# Carrier-Board-CM740.net
KiCad netlist of a schematic drawn in EAGLE
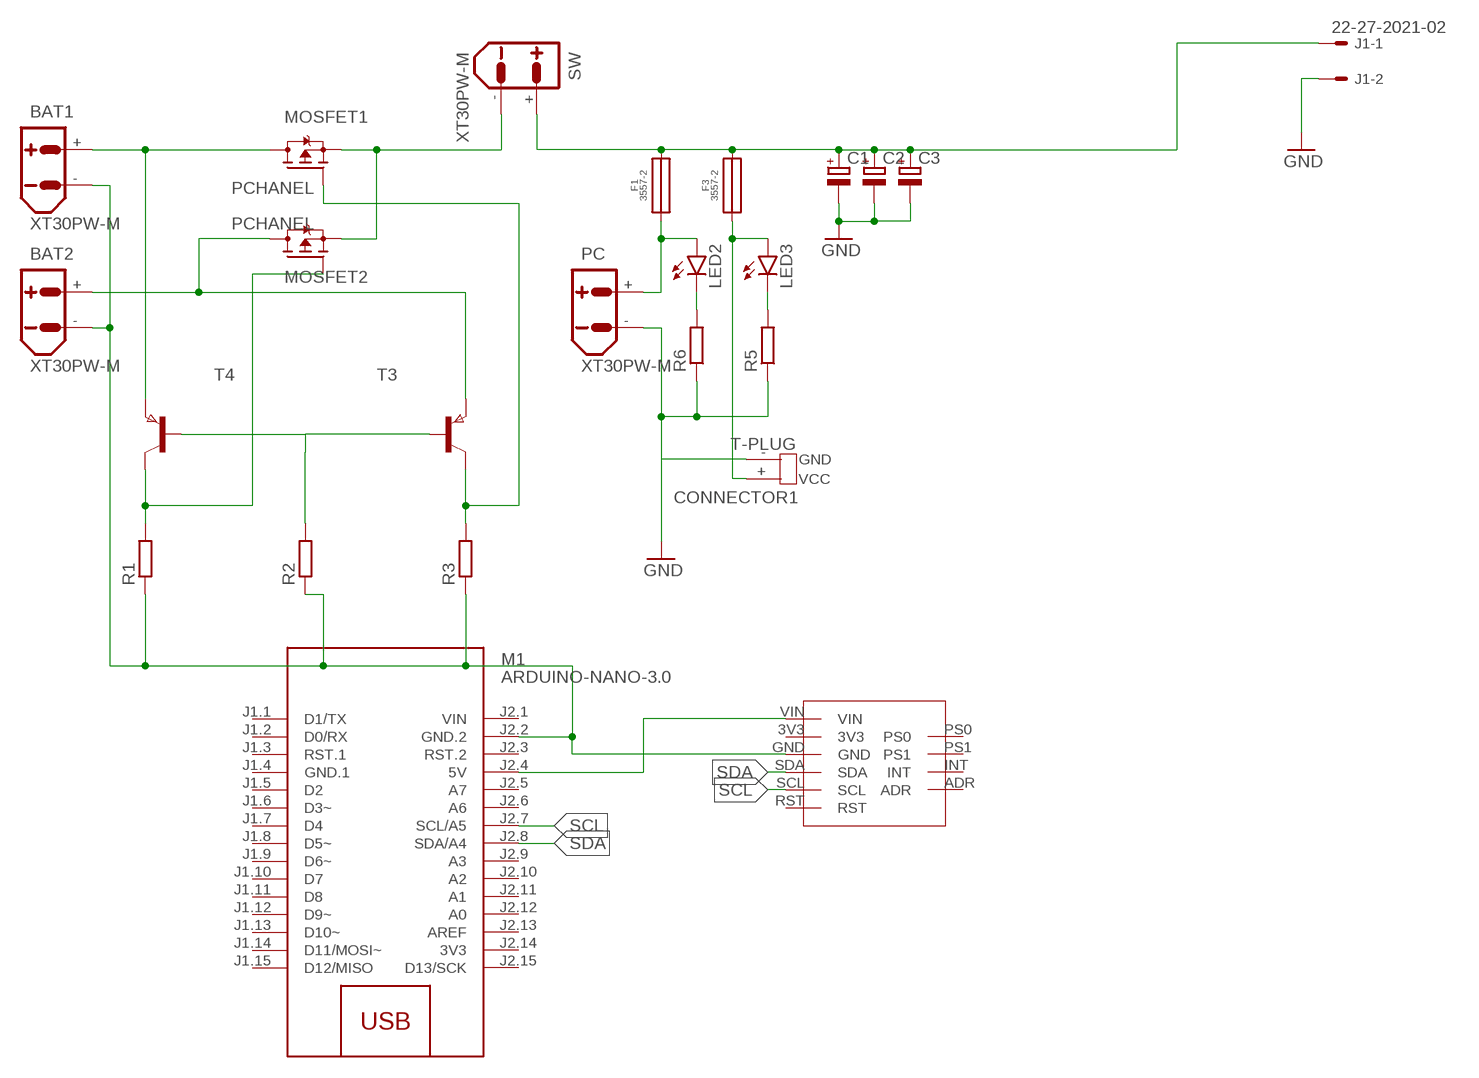
[diagram p0: schematic, sheet 1]

(export (version "E")
  (design (tool "Eeschema 10.0.6"))
  (components
    (comp (ref "BAT1")
      (value "XT30PW-M")
      (footprint "eagle-import:XT30PW-M")
      (libsource (lib "eagle-import") (part "XT30PW-M"))
    )
    (comp (ref "BAT2")
      (value "XT30PW-M")
      (footprint "eagle-import:XT30PW-M")
      (libsource (lib "eagle-import") (part "XT30PW-M"))
    )
    (comp (ref "C1")
      (value "CPOL-EU150CLZ-1014")
      (footprint "eagle-import:150CLZ-1014")
      (libsource (lib "eagle-import") (part "CPOL-EU150CLZ-1014"))
    )
    (comp (ref "C2")
      (value "CPOL-EU150CLZ-1014")
      (footprint "eagle-import:150CLZ-1014")
      (libsource (lib "eagle-import") (part "CPOL-EU150CLZ-1014"))
    )
    (comp (ref "C3")
      (value "CPOL-EU150CLZ-1014")
      (footprint "eagle-import:150CLZ-1014")
      (libsource (lib "eagle-import") (part "CPOL-EU150CLZ-1014"))
    )
    (comp (ref "CONNECTOR1")
      (value "T-PLUG")
      (footprint "eagle-import:T-PLUG")
      (libsource (lib "eagle-import") (part "T-PLUG"))
    )
    (comp (ref "F1")
      (value "3557-2")
      (footprint "eagle-import:3557-2")
      (libsource (lib "eagle-import") (part "3557-2"))
    )
    (comp (ref "F3")
      (value "3557-2")
      (footprint "eagle-import:3557-2")
      (libsource (lib "eagle-import") (part "3557-2"))
    )
    (comp (ref "J1")
      (value "22-27-2021-02")
      (footprint "eagle-import:6410-02")
      (fields (field (name "MF") "MOLEX"))
      (libsource (lib "eagle-import") (part "22-?-0227-2021"))
    )
    (comp (ref "LED2")
      (value "LEDCHIP-LED0805")
      (footprint "eagle-import:CHIP-LED0805")
      (libsource (lib "eagle-import") (part "LEDCHIP-LED0805"))
    )
    (comp (ref "LED3")
      (value "LEDCHIP-LED0805")
      (footprint "eagle-import:CHIP-LED0805")
      (libsource (lib "eagle-import") (part "LEDCHIP-LED0805"))
    )
    (comp (ref "M1")
      (value "ARDUINO-NANO-3.0")
      (footprint "eagle-import:ARDUINO-NANO-3.0")
      (libsource (lib "eagle-import") (part "ARDUINO-NANO-3.0"))
    )
    (comp (ref "MOSFET1")
      (value "PCHANEL")
      (footprint "eagle-import:TO252")
      (libsource (lib "eagle-import") (part "FDD4141TO252"))
    )
    (comp (ref "MOSFET2")
      (value "PCHANEL")
      (footprint "eagle-import:TO252")
      (libsource (lib "eagle-import") (part "FDD4141TO252"))
    )
    (comp (ref "PC")
      (value "XT30PW-M")
      (footprint "eagle-import:XT30PW-M")
      (libsource (lib "eagle-import") (part "XT30PW-M"))
    )
    (comp (ref "R1")
      (value "R-EU_R1206")
      (footprint "eagle-import:R1206")
      (libsource (lib "eagle-import") (part "R-EU_R1206"))
    )
    (comp (ref "R2")
      (value "R-EU_R1206")
      (footprint "eagle-import:R1206")
      (libsource (lib "eagle-import") (part "R-EU_R1206"))
    )
    (comp (ref "R3")
      (value "R-EU_R1206")
      (footprint "eagle-import:R1206")
      (libsource (lib "eagle-import") (part "R-EU_R1206"))
    )
    (comp (ref "R5")
      (value "R-EU_M0805")
      (footprint "eagle-import:M0805")
      (libsource (lib "eagle-import") (part "R-EU_M0805"))
    )
    (comp (ref "R6")
      (value "R-EU_M0805")
      (footprint "eagle-import:M0805")
      (libsource (lib "eagle-import") (part "R-EU_M0805"))
    )
    (comp (ref "SW")
      (value "XT30PW-M")
      (footprint "eagle-import:XT30PW-M")
      (libsource (lib "eagle-import") (part "XT30PW-M"))
    )
    (comp (ref "T3")
      (value "PNPSOT23")
      (footprint "eagle-import:SOT-23")
      (fields (field (name "MPN") "DSS20200L-7"))
      (libsource (lib "eagle-import") (part "PNPSOT23"))
    )
    (comp (ref "T4")
      (value "PNPSOT23")
      (footprint "eagle-import:SOT-23")
      (fields (field (name "MPN") "DSS20200L-7"))
      (libsource (lib "eagle-import") (part "PNPSOT23"))
    )
    (comp (ref "U$1")
      (value "BNO055_BNO055")
      (footprint "eagle-import:BNO055_BNO055")
      (libsource (lib "eagle-import") (part "BNO055_BNO055"))
    )
  )
  (nets
    (net (code "1") (name "/3V3") (class "Default")
      (node (ref "M1") (pin "J2.14") (pinfunction "3V3_J2.14") (pintype "power_in"))
    )
    (net (code "2") (name "/GND.1") (class "Default")
      (node (ref "M1") (pin "J1.4") (pinfunction "GND.1_J1.4") (pintype "power_in"))
    )
    (net (code "3") (name "/VIN") (class "Default")
      (node (ref "M1") (pin "J2.1") (pinfunction "VIN_J2.1") (pintype "power_in"))
    )
    (net (code "4") (name "GND") (class "Default")
      (node (ref "BAT1") (pin "-") (pinfunction "-_-") (pintype "power_in"))
      (node (ref "BAT2") (pin "-") (pinfunction "-_-") (pintype "power_in"))
      (node (ref "C1") (pin "-") (pinfunction "-_-") (pintype "passive"))
      (node (ref "C2") (pin "-") (pinfunction "-_-") (pintype "passive"))
      (node (ref "C3") (pin "-") (pinfunction "-_-") (pintype "passive"))
      (node (ref "CONNECTOR1") (pin "-") (pinfunction "GND_-") (pintype "power_in"))
      (node (ref "J1") (pin "2") (pinfunction "S_2") (pintype "passive"))
      (node (ref "M1") (pin "J2.2") (pinfunction "GND.2_J2.2") (pintype "power_in"))
      (node (ref "PC") (pin "-") (pinfunction "-_-") (pintype "power_in"))
      (node (ref "R1") (pin "1") (pinfunction "1_1") (pintype "passive"))
      (node (ref "R2") (pin "1") (pinfunction "1_1") (pintype "passive"))
      (node (ref "R3") (pin "1") (pinfunction "1_1") (pintype "passive"))
      (node (ref "R5") (pin "1") (pinfunction "1_1") (pintype "passive"))
      (node (ref "R6") (pin "1") (pinfunction "1_1") (pintype "passive"))
      (node (ref "U$1") (pin "GND") (pinfunction "GND_GND") (pintype "bidirectional"))
    )
    (net (code "5") (name "Net-(CONNECTOR1-VCC)") (class "Default")
      (node (ref "CONNECTOR1") (pin "+") (pinfunction "VCC_+") (pintype "power_in"))
      (node (ref "F3") (pin "1") (pinfunction "1_1") (pintype "bidirectional"))
      (node (ref "F3") (pin "2") (pinfunction "1_2") (pintype "bidirectional"))
      (node (ref "LED3") (pin "A") (pinfunction "A_A") (pintype "passive"))
    )
    (net (code "6") (name "Net-(F1-1-Pad2)") (class "Default")
      (node (ref "F1") (pin "1") (pinfunction "1_1") (pintype "bidirectional"))
      (node (ref "F1") (pin "2") (pinfunction "1_2") (pintype "bidirectional"))
      (node (ref "LED2") (pin "A") (pinfunction "A_A") (pintype "passive"))
      (node (ref "PC") (pin "+") (pinfunction "+_+") (pintype "power_in"))
    )
    (net (code "7") (name "Net-(J1A-S)") (class "Default")
      (node (ref "C1") (pin "+") (pinfunction "+_+") (pintype "passive"))
      (node (ref "C2") (pin "+") (pinfunction "+_+") (pintype "passive"))
      (node (ref "C3") (pin "+") (pinfunction "+_+") (pintype "passive"))
      (node (ref "F1") (pin "3") (pinfunction "2_3") (pintype "bidirectional"))
      (node (ref "F1") (pin "4") (pinfunction "2_4") (pintype "bidirectional"))
      (node (ref "F3") (pin "3") (pinfunction "2_3") (pintype "bidirectional"))
      (node (ref "F3") (pin "4") (pinfunction "2_4") (pintype "bidirectional"))
      (node (ref "J1") (pin "1") (pinfunction "S_1") (pintype "passive"))
      (node (ref "SW") (pin "+") (pinfunction "+_+") (pintype "power_in"))
    )
    (net (code "8") (name "Net-(LED2-PadC)") (class "Default")
      (node (ref "LED2") (pin "C") (pinfunction "C_C") (pintype "passive"))
      (node (ref "R6") (pin "2") (pinfunction "2_2") (pintype "passive"))
    )
    (net (code "9") (name "Net-(LED3-PadC)") (class "Default")
      (node (ref "LED3") (pin "C") (pinfunction "C_C") (pintype "passive"))
      (node (ref "R5") (pin "2") (pinfunction "2_2") (pintype "passive"))
    )
    (net (code "10") (name "Net-(M1-5V)") (class "Default")
      (node (ref "M1") (pin "J2.4") (pinfunction "5V_J2.4") (pintype "power_in"))
      (node (ref "U$1") (pin "VIN") (pinfunction "VIN_VIN") (pintype "bidirectional"))
    )
    (net (code "11") (name "Net-(MOSFET1-D)") (class "Default")
      (node (ref "BAT1") (pin "+") (pinfunction "+_+") (pintype "power_in"))
      (node (ref "MOSFET1") (pin "3") (pinfunction "D_3") (pintype "passive"))
      (node (ref "T4") (pin "2") (pinfunction "E_2") (pintype "passive"))
    )
    (net (code "12") (name "Net-(MOSFET1-G)") (class "Default")
      (node (ref "MOSFET1") (pin "1") (pinfunction "G_1") (pintype "passive"))
      (node (ref "R3") (pin "2") (pinfunction "2_2") (pintype "passive"))
      (node (ref "T3") (pin "1") (pinfunction "C_1") (pintype "passive"))
    )
    (net (code "13") (name "Net-(MOSFET1-S)") (class "Default")
      (node (ref "MOSFET1") (pin "2") (pinfunction "S_2") (pintype "passive"))
      (node (ref "MOSFET2") (pin "2") (pinfunction "S_2") (pintype "passive"))
      (node (ref "SW") (pin "-") (pinfunction "-_-") (pintype "power_in"))
    )
    (net (code "14") (name "Net-(MOSFET2-D)") (class "Default")
      (node (ref "BAT2") (pin "+") (pinfunction "+_+") (pintype "power_in"))
      (node (ref "MOSFET2") (pin "3") (pinfunction "D_3") (pintype "passive"))
      (node (ref "T3") (pin "2") (pinfunction "E_2") (pintype "passive"))
    )
    (net (code "15") (name "Net-(MOSFET2-G)") (class "Default")
      (node (ref "MOSFET2") (pin "1") (pinfunction "G_1") (pintype "passive"))
      (node (ref "R1") (pin "2") (pinfunction "2_2") (pintype "passive"))
      (node (ref "T4") (pin "1") (pinfunction "C_1") (pintype "passive"))
    )
    (net (code "16") (name "Net-(T3-B)") (class "Default")
      (node (ref "R2") (pin "2") (pinfunction "2_2") (pintype "passive"))
      (node (ref "T3") (pin "3") (pinfunction "B_3") (pintype "passive"))
      (node (ref "T4") (pin "3") (pinfunction "B_3") (pintype "passive"))
    )
    (net (code "17") (name "SCL") (class "Default")
      (node (ref "M1") (pin "J2.7") (pinfunction "SCL/A5_J2.7") (pintype "bidirectional"))
      (node (ref "U$1") (pin "SCL") (pinfunction "SCL_SCL") (pintype "bidirectional"))
    )
    (net (code "18") (name "SDA") (class "Default")
      (node (ref "M1") (pin "J2.8") (pinfunction "SDA/A4_J2.8") (pintype "bidirectional"))
      (node (ref "U$1") (pin "SDA") (pinfunction "SDA_SDA") (pintype "bidirectional"))
    )
    (net (code "19") (name "unconnected-(M1-A0-PadJ2.12)") (class "Default")
      (node (ref "M1") (pin "J2.12") (pinfunction "A0_J2.12") (pintype "bidirectional"))
    )
    (net (code "20") (name "unconnected-(M1-A1-PadJ2.11)") (class "Default")
      (node (ref "M1") (pin "J2.11") (pinfunction "A1_J2.11") (pintype "bidirectional"))
    )
    (net (code "21") (name "unconnected-(M1-A2-PadJ2.10)") (class "Default")
      (node (ref "M1") (pin "J2.10") (pinfunction "A2_J2.10") (pintype "bidirectional"))
    )
    (net (code "22") (name "unconnected-(M1-A3-PadJ2.9)") (class "Default")
      (node (ref "M1") (pin "J2.9") (pinfunction "A3_J2.9") (pintype "bidirectional"))
    )
    (net (code "23") (name "unconnected-(M1-A6-PadJ2.6)") (class "Default")
      (node (ref "M1") (pin "J2.6") (pinfunction "A6_J2.6") (pintype "bidirectional"))
    )
    (net (code "24") (name "unconnected-(M1-A7-PadJ2.5)") (class "Default")
      (node (ref "M1") (pin "J2.5") (pinfunction "A7_J2.5") (pintype "bidirectional"))
    )
    (net (code "25") (name "unconnected-(M1-AREF-PadJ2.13)") (class "Default")
      (node (ref "M1") (pin "J2.13") (pinfunction "AREF_J2.13") (pintype "bidirectional"))
    )
    (net (code "26") (name "unconnected-(M1-D0{slash}RX-PadJ1.2)") (class "Default")
      (node (ref "M1") (pin "J1.2") (pinfunction "D0/RX_J1.2") (pintype "bidirectional"))
    )
    (net (code "27") (name "unconnected-(M1-D1{slash}TX-PadJ1.1)") (class "Default")
      (node (ref "M1") (pin "J1.1") (pinfunction "D1/TX_J1.1") (pintype "bidirectional"))
    )
    (net (code "28") (name "unconnected-(M1-D2-PadJ1.5)") (class "Default")
      (node (ref "M1") (pin "J1.5") (pinfunction "D2_J1.5") (pintype "bidirectional"))
    )
    (net (code "29") (name "unconnected-(M1-D3~{}-PadJ1.6)") (class "Default")
      (node (ref "M1") (pin "J1.6") (pinfunction "D3~{}_J1.6") (pintype "bidirectional"))
    )
    (net (code "30") (name "unconnected-(M1-D4-PadJ1.7)") (class "Default")
      (node (ref "M1") (pin "J1.7") (pinfunction "D4_J1.7") (pintype "bidirectional"))
    )
    (net (code "31") (name "unconnected-(M1-D5~{}-PadJ1.8)") (class "Default")
      (node (ref "M1") (pin "J1.8") (pinfunction "D5~{}_J1.8") (pintype "bidirectional"))
    )
    (net (code "32") (name "unconnected-(M1-D6~{}-PadJ1.9)") (class "Default")
      (node (ref "M1") (pin "J1.9") (pinfunction "D6~{}_J1.9") (pintype "bidirectional"))
    )
    (net (code "33") (name "unconnected-(M1-D7-PadJ1.10)") (class "Default")
      (node (ref "M1") (pin "J1.10") (pinfunction "D7_J1.10") (pintype "bidirectional"))
    )
    (net (code "34") (name "unconnected-(M1-D8-PadJ1.11)") (class "Default")
      (node (ref "M1") (pin "J1.11") (pinfunction "D8_J1.11") (pintype "bidirectional"))
    )
    (net (code "35") (name "unconnected-(M1-D9~{}-PadJ1.12)") (class "Default")
      (node (ref "M1") (pin "J1.12") (pinfunction "D9~{}_J1.12") (pintype "bidirectional"))
    )
    (net (code "36") (name "unconnected-(M1-D10~{}-PadJ1.13)") (class "Default")
      (node (ref "M1") (pin "J1.13") (pinfunction "D10~{}_J1.13") (pintype "bidirectional"))
    )
    (net (code "37") (name "unconnected-(M1-D11{slash}MOSI~{}-PadJ1.14)") (class "Default")
      (node (ref "M1") (pin "J1.14") (pinfunction "D11/MOSI~{}_J1.14") (pintype "bidirectional"))
    )
    (net (code "38") (name "unconnected-(M1-D12{slash}MISO-PadJ1.15)") (class "Default")
      (node (ref "M1") (pin "J1.15") (pinfunction "D12/MISO_J1.15") (pintype "bidirectional"))
    )
    (net (code "39") (name "unconnected-(M1-D13{slash}SCK-PadJ2.15)") (class "Default")
      (node (ref "M1") (pin "J2.15") (pinfunction "D13/SCK_J2.15") (pintype "bidirectional"))
    )
    (net (code "40") (name "unconnected-(M1-RST.1-PadJ1.3)") (class "Default")
      (node (ref "M1") (pin "J1.3") (pinfunction "RST.1_J1.3") (pintype "bidirectional"))
    )
    (net (code "41") (name "unconnected-(M1-RST.2-PadJ2.3)") (class "Default")
      (node (ref "M1") (pin "J2.3") (pinfunction "RST.2_J2.3") (pintype "bidirectional"))
    )
    (net (code "42") (name "unconnected-(U$1-Pad3V3)") (class "Default")
      (node (ref "U$1") (pin "3V3") (pinfunction "3V3_3V3") (pintype "bidirectional"))
    )
    (net (code "43") (name "unconnected-(U$1-PadADR)") (class "Default")
      (node (ref "U$1") (pin "ADR") (pinfunction "ADR_ADR") (pintype "bidirectional"))
    )
    (net (code "44") (name "unconnected-(U$1-PadINT)") (class "Default")
      (node (ref "U$1") (pin "INT") (pinfunction "INT_INT") (pintype "bidirectional"))
    )
    (net (code "45") (name "unconnected-(U$1-PadPS0)") (class "Default")
      (node (ref "U$1") (pin "PS0") (pinfunction "PS0_PS0") (pintype "bidirectional"))
    )
    (net (code "46") (name "unconnected-(U$1-PadPS1)") (class "Default")
      (node (ref "U$1") (pin "PS1") (pinfunction "PS1_PS1") (pintype "bidirectional"))
    )
    (net (code "47") (name "unconnected-(U$1-PadRST)") (class "Default")
      (node (ref "U$1") (pin "RST") (pinfunction "RST_RST") (pintype "bidirectional"))
    )
  )
)
